# CONN.net
KiCad netlist of a schematic drawn in Altium Designer
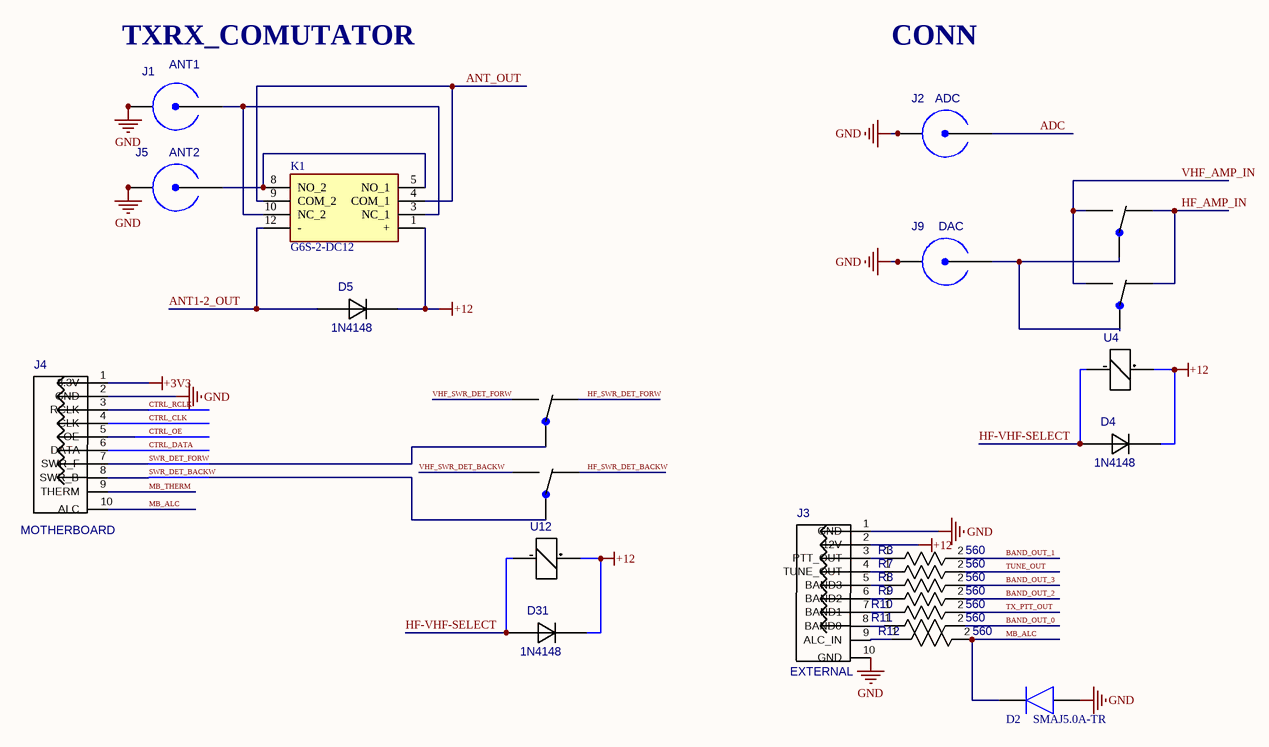
[diagram p0: CONN.SchDoc]

(export (version "E")
  (design (tool "Eeschema 10.0.6"))
  (components
    (comp (ref "D2")
      (value "SMAJ5.0A-TR")
      (footprint "SMBJ36CATR")
      (description "Diode")
      (fields
        (field (name "MANUFACTURER_PART_NUMBER") "SMLVT3V3")
        (field (name "MOUSER PART NUMBER") "511-SMLVT3V3")
      )
      (libsource (lib "RF-UNIT-BIG") (part "SMLVT3V3"))
    )
    (comp (ref "D4") (value "1N4148") (footprint "SS14") (libsource (lib "RF-UNIT-BIG") (part "1N4148")))
    (comp (ref "D5") (value "1N4148") (footprint "SS14") (libsource (lib "RF-UNIT-BIG") (part "1N4148")))
    (comp (ref "D31") (value "1N4148") (footprint "SS14") (libsource (lib "RF-UNIT-BIG") (part "1N4148")))
    (comp (ref "J1")
      (value "ANT1")
      (footprint "31-5431")
      (description "SMA")
      (libsource (lib "RF-UNIT_1") (part "31-5431"))
    )
    (comp (ref "J2")
      (value "ADC")
      (footprint "31-5431")
      (description "SMA")
      (libsource (lib "RF-UNIT_1") (part "31-5431"))
    )
    (comp (ref "J3")
      (value "EXTERNAL")
      (footprint "90131-0126")
      (description "2*5 PIN")
      (libsource (lib "RF-UNIT") (part "90131-0126"))
    )
    (comp (ref "J4")
      (value "MOTHERBOARD")
      (footprint "90131-0126")
      (description "2*5 PIN")
      (libsource (lib "RF-UNIT") (part "90131-0126"))
    )
    (comp (ref "J5")
      (value "ANT2")
      (footprint "31-5431")
      (description "SMA")
      (libsource (lib "RF-UNIT_1") (part "31-5431"))
    )
    (comp (ref "J9")
      (value "DAC")
      (footprint "31-5431")
      (description "SMA")
      (libsource (lib "RF-UNIT_1") (part "31-5431"))
    )
    (comp (ref "K1")
      (value "G6S-2-DC12")
      (footprint "SamacSys:G6S2DC12")
      (description "Relay or Contactor")
      (fields (field (name "MOUSER PART NUMBER") "653-G6S-2-DC12A"))
      (libsource (lib "*") (part "G6S-2-DC12"))
    )
    (comp (ref "R3")
      (value "560")
      (footprint "RES_0805")
      (description "RES_0805")
      (libsource (lib "*") (part "RES_0805"))
    )
    (comp (ref "R7")
      (value "560")
      (footprint "RES_0805")
      (description "RES_0805")
      (libsource (lib "*") (part "RES_0805"))
    )
    (comp (ref "R8")
      (value "560")
      (footprint "RES_0805")
      (description "RES_0805")
      (libsource (lib "*") (part "RES_0805"))
    )
    (comp (ref "R9")
      (value "560")
      (footprint "RES_0805")
      (description "RES_0805")
      (libsource (lib "*") (part "RES_0805"))
    )
    (comp (ref "R10")
      (value "560")
      (footprint "RES_0805")
      (description "RES_0805")
      (libsource (lib "*") (part "RES_0805"))
    )
    (comp (ref "R11")
      (value "560")
      (footprint "RES_0805")
      (description "RES_0805")
      (libsource (lib "*") (part "RES_0805"))
    )
    (comp (ref "R12")
      (value "560")
      (footprint "RES_0805")
      (description "RES_0805")
      (libsource (lib "*") (part "RES_0805"))
    )
    (comp (ref "U4")
      (value "Axicom IM06")
      (footprint "IM06GR")
      (libsource (lib "RF-UNIT-BIG") (part "Axicom IM06"))
    )
    (comp (ref "U12")
      (value "Axicom IM06")
      (footprint "IM06GR")
      (libsource (lib "RF-UNIT-BIG") (part "Axicom IM06"))
    )
  )
  (nets
    (net (code "1") (name "+3V3") (class "Default")
      (node (ref "J4") (pin "1") (pinfunction "3.3V_1") (pintype "passive"))
    )
    (net (code "2") (name "+12") (class "Default")
      (node (ref "D31") (pin "1") (pinfunction "K_1") (pintype "passive"))
      (node (ref "D4") (pin "1") (pinfunction "K_1") (pintype "passive"))
      (node (ref "D5") (pin "1") (pinfunction "K_1") (pintype "passive"))
      (node (ref "J3") (pin "2") (pinfunction "GND_2") (pintype "passive"))
      (node (ref "K1") (pin "1") (pinfunction "+_1") (pintype "passive"))
      (node (ref "U12") (pin "1") (pinfunction "+_1") (pintype "passive"))
      (node (ref "U4") (pin "1") (pinfunction "+_1") (pintype "passive"))
    )
    (net (code "4") (name "/ADC") (class "Default")
      (node (ref "J2") (pin "5") (pinfunction "CON_5") (pintype "passive"))
    )
    (net (code "5") (name "/ANT1-2_OUT") (class "Default")
      (node (ref "D5") (pin "2") (pinfunction "A_2") (pintype "passive"))
      (node (ref "K1") (pin "12") (pinfunction "-_12") (pintype "passive"))
    )
    (net (code "6") (name "/ANT_OUT") (class "Default")
      (node (ref "K1") (pin "4") (pinfunction "COM_1_4") (pintype "passive"))
      (node (ref "K1") (pin "9") (pinfunction "COM_2_9") (pintype "passive"))
    )
    (net (code "7") (name "/BAND_OUT_0") (class "Default")
      (node (ref "R11") (pin "2") (pinfunction "2_2") (pintype "passive"))
    )
    (net (code "8") (name "/BAND_OUT_1") (class "Default")
      (node (ref "R3") (pin "2") (pinfunction "2_2") (pintype "passive"))
    )
    (net (code "9") (name "/BAND_OUT_2") (class "Default")
      (node (ref "R9") (pin "2") (pinfunction "2_2") (pintype "passive"))
    )
    (net (code "10") (name "/BAND_OUT_3") (class "Default")
      (node (ref "R8") (pin "2") (pinfunction "2_2") (pintype "passive"))
    )
    (net (code "11") (name "/CTRL_CLK") (class "Default")
      (node (ref "J4") (pin "4") (pinfunction "CLK_4") (pintype "passive"))
    )
    (net (code "12") (name "/CTRL_DATA") (class "Default")
      (node (ref "J4") (pin "6") (pinfunction "DATA_6") (pintype "passive"))
    )
    (net (code "13") (name "/CTRL_OE") (class "Default")
      (node (ref "J4") (pin "5") (pinfunction "OE_5") (pintype "passive"))
    )
    (net (code "14") (name "/CTRL_RCLK") (class "Default")
      (node (ref "J4") (pin "3") (pinfunction "RCLK_3") (pintype "passive"))
    )
    (net (code "15") (name "/HF-VHF-SELECT") (class "Default")
      (node (ref "D31") (pin "2") (pinfunction "A_2") (pintype "passive"))
      (node (ref "D4") (pin "2") (pinfunction "A_2") (pintype "passive"))
      (node (ref "U12") (pin "8") (pinfunction "-_8") (pintype "passive"))
      (node (ref "U4") (pin "8") (pinfunction "-_8") (pintype "passive"))
    )
    (net (code "16") (name "/HF_AMP_IN") (class "Default")
      (node (ref "U4") (pin "2") (pinfunction "O_2") (pintype "passive"))
      (node (ref "U4") (pin "7") (pinfunction "O_7") (pintype "passive"))
    )
    (net (code "17") (name "/HF_SWR_DET_BACKW") (class "Default")
      (node (ref "U12") (pin "2") (pinfunction "O_2") (pintype "passive"))
    )
    (net (code "18") (name "/HF_SWR_DET_FORW") (class "Default")
      (node (ref "U12") (pin "7") (pinfunction "O_7") (pintype "passive"))
    )
    (net (code "19") (name "/MB_ALC") (class "Default")
      (node (ref "D2") (pin "1") (pinfunction "K_1") (pintype "passive"))
      (node (ref "J4") (pin "10") (pinfunction "ALC_10") (pintype "passive"))
      (node (ref "R12") (pin "2") (pinfunction "2_2") (pintype "passive"))
    )
    (net (code "20") (name "/MB_THERM") (class "Default")
      (node (ref "J4") (pin "9") (pinfunction "THERM_9") (pintype "passive"))
    )
    (net (code "21") (name "/SWR_DET_BACKW") (class "Default")
      (node (ref "J4") (pin "8") (pinfunction "SWR_B_8") (pintype "passive"))
      (node (ref "U12") (pin "3") (pinfunction "P_3") (pintype "passive"))
    )
    (net (code "22") (name "/SWR_DET_FORW") (class "Default")
      (node (ref "J4") (pin "7") (pinfunction "SWR_F_7") (pintype "passive"))
      (node (ref "U12") (pin "6") (pinfunction "P_6") (pintype "passive"))
    )
    (net (code "23") (name "/TUNE_OUT") (class "Default")
      (node (ref "R7") (pin "2") (pinfunction "2_2") (pintype "passive"))
    )
    (net (code "24") (name "/TX_PTT_OUT") (class "Default")
      (node (ref "R10") (pin "2") (pinfunction "2_2") (pintype "passive"))
    )
    (net (code "25") (name "/VHF_AMP_IN") (class "Default")
      (node (ref "U4") (pin "4") (pinfunction "S_4") (pintype "passive"))
      (node (ref "U4") (pin "5") (pinfunction "S_5") (pintype "passive"))
    )
    (net (code "26") (name "/VHF_SWR_DET_BACKW") (class "Default")
      (node (ref "U12") (pin "4") (pinfunction "S_4") (pintype "passive"))
    )
    (net (code "27") (name "/VHF_SWR_DET_FORW") (class "Default")
      (node (ref "U12") (pin "5") (pinfunction "S_5") (pintype "passive"))
    )
    (net (code "28") (name "GND") (class "Default")
      (node (ref "D2") (pin "2") (pinfunction "A_2") (pintype "passive"))
      (node (ref "J1") (pin "1") (pinfunction "GND_1") (pintype "passive"))
      (node (ref "J1") (pin "2") (pinfunction "GND_2") (pintype "passive"))
      (node (ref "J1") (pin "3") (pinfunction "GND_3") (pintype "passive"))
      (node (ref "J1") (pin "4") (pinfunction "GND_4") (pintype "passive"))
      (node (ref "J2") (pin "1") (pinfunction "GND_1") (pintype "passive"))
      (node (ref "J2") (pin "2") (pinfunction "GND_2") (pintype "passive"))
      (node (ref "J2") (pin "3") (pinfunction "GND_3") (pintype "passive"))
      (node (ref "J2") (pin "4") (pinfunction "GND_4") (pintype "passive"))
      (node (ref "J3") (pin "1") (pinfunction "3.3V_1") (pintype "passive"))
      (node (ref "J3") (pin "10") (pinfunction "ALC_10") (pintype "passive"))
      (node (ref "J4") (pin "2") (pinfunction "GND_2") (pintype "passive"))
      (node (ref "J5") (pin "1") (pinfunction "GND_1") (pintype "passive"))
      (node (ref "J5") (pin "2") (pinfunction "GND_2") (pintype "passive"))
      (node (ref "J5") (pin "3") (pinfunction "GND_3") (pintype "passive"))
      (node (ref "J5") (pin "4") (pinfunction "GND_4") (pintype "passive"))
      (node (ref "J9") (pin "1") (pinfunction "GND_1") (pintype "passive"))
      (node (ref "J9") (pin "2") (pinfunction "GND_2") (pintype "passive"))
      (node (ref "J9") (pin "3") (pinfunction "GND_3") (pintype "passive"))
      (node (ref "J9") (pin "4") (pinfunction "GND_4") (pintype "passive"))
    )
    (net (code "29") (name "Net-(J1-CON)") (class "Default")
      (node (ref "J1") (pin "5") (pinfunction "CON_5") (pintype "passive"))
      (node (ref "K1") (pin "10") (pinfunction "NC_2_10") (pintype "passive"))
      (node (ref "K1") (pin "3") (pinfunction "NC_1_3") (pintype "passive"))
    )
    (net (code "30") (name "Net-(J3-CLK)") (class "Default")
      (node (ref "J3") (pin "4") (pinfunction "CLK_4") (pintype "passive"))
      (node (ref "R7") (pin "1") (pinfunction "1_1") (pintype "passive"))
    )
    (net (code "31") (name "Net-(J3-DATA)") (class "Default")
      (node (ref "J3") (pin "6") (pinfunction "DATA_6") (pintype "passive"))
      (node (ref "R9") (pin "1") (pinfunction "1_1") (pintype "passive"))
    )
    (net (code "32") (name "Net-(J3-OE)") (class "Default")
      (node (ref "J3") (pin "5") (pinfunction "OE_5") (pintype "passive"))
      (node (ref "R8") (pin "1") (pinfunction "1_1") (pintype "passive"))
    )
    (net (code "33") (name "Net-(J3-RCLK)") (class "Default")
      (node (ref "J3") (pin "3") (pinfunction "RCLK_3") (pintype "passive"))
      (node (ref "R3") (pin "1") (pinfunction "1_1") (pintype "passive"))
    )
    (net (code "34") (name "Net-(J3-SWR_B)") (class "Default")
      (node (ref "J3") (pin "8") (pinfunction "SWR_B_8") (pintype "passive"))
      (node (ref "R11") (pin "1") (pinfunction "1_1") (pintype "passive"))
    )
    (net (code "35") (name "Net-(J3-SWR_F)") (class "Default")
      (node (ref "J3") (pin "7") (pinfunction "SWR_F_7") (pintype "passive"))
      (node (ref "R10") (pin "1") (pinfunction "1_1") (pintype "passive"))
    )
    (net (code "36") (name "Net-(J3-THERM)") (class "Default")
      (node (ref "J3") (pin "9") (pinfunction "THERM_9") (pintype "passive"))
      (node (ref "R12") (pin "1") (pinfunction "1_1") (pintype "passive"))
    )
    (net (code "37") (name "Net-(J5-CON)") (class "Default")
      (node (ref "J5") (pin "5") (pinfunction "CON_5") (pintype "passive"))
      (node (ref "K1") (pin "5") (pinfunction "NO_1_5") (pintype "passive"))
      (node (ref "K1") (pin "8") (pinfunction "NO_2_8") (pintype "passive"))
    )
    (net (code "38") (name "Net-(J9-CON)") (class "Default")
      (node (ref "J9") (pin "5") (pinfunction "CON_5") (pintype "passive"))
      (node (ref "U4") (pin "3") (pinfunction "P_3") (pintype "passive"))
      (node (ref "U4") (pin "6") (pinfunction "P_6") (pintype "passive"))
    )
  )
)
